# avrkitOnly.net
KiCad netlist of a schematic drawn in EAGLE
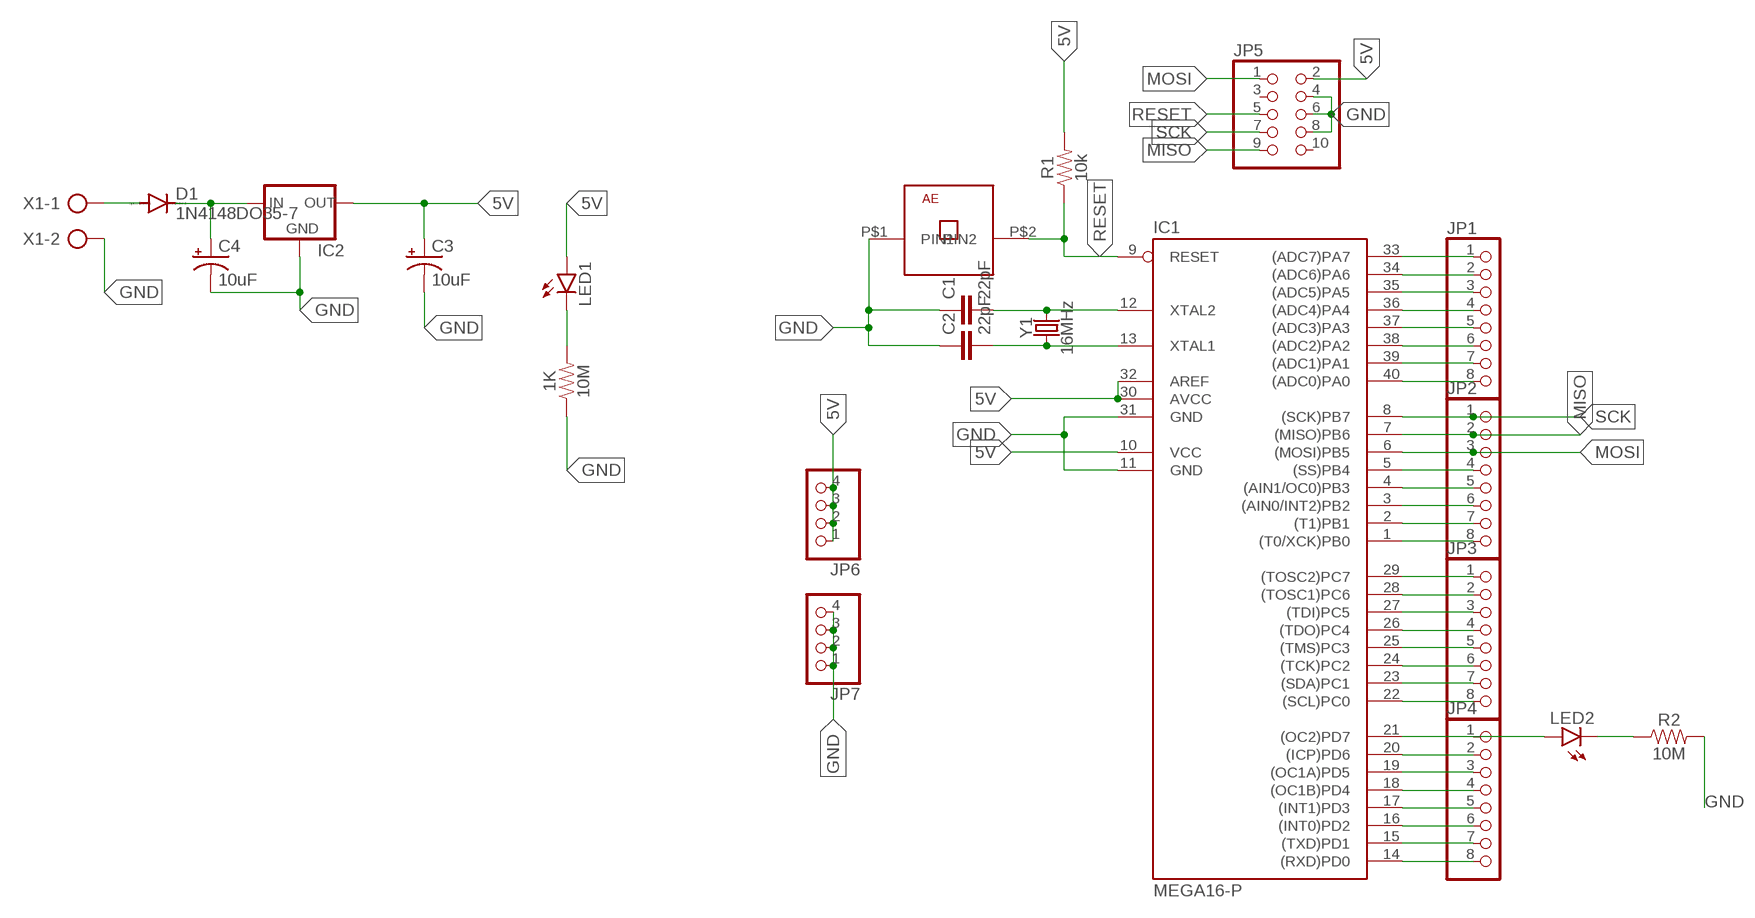
[diagram p0: schematic, sheet 1]

(export (version "E")
  (design (tool "Eeschema 10.0.6"))
  (components
    (comp (ref "1K")
      (value "10M")
      (footprint "eagle-import:AXIAL-0.3")
      (libsource (lib "eagle-import") (part "10MOHM-HORIZ-1/4W-5%"))
    )
    (comp (ref "C1")
      (value "22pF")
      (footprint "eagle-import:CAP-PTH-2.54")
      (libsource (lib "eagle-import") (part "22PF-PTH-2.54MM-200V-5%"))
    )
    (comp (ref "C2")
      (value "22pF")
      (footprint "eagle-import:CAP-PTH-2.54")
      (libsource (lib "eagle-import") (part "22PF-PTH-2.54MM-200V-5%"))
    )
    (comp (ref "C3")
      (value "10uF")
      (footprint "eagle-import:CPOL-RADIAL-2.5MM-5MM")
      (libsource (lib "eagle-import") (part "10UF-POLAR-RADIAL-2.5MM-25V-20%"))
    )
    (comp (ref "C4")
      (value "10uF")
      (footprint "eagle-import:CPOL-RADIAL-2.5MM-5MM")
      (libsource (lib "eagle-import") (part "10UF-POLAR-RADIAL-2.5MM-25V-20%"))
    )
    (comp (ref "D1")
      (value "1N4148DO35-7")
      (footprint "eagle-import:DO35-7")
      (libsource (lib "eagle-import") (part "1N4148DO35-7"))
    )
    (comp (ref "IC1")
      (value "MEGA16-P")
      (footprint "eagle-import:DIL40")
      (fields (field (name "MPN") "ATMEGA16-16PU"))
      (libsource (lib "eagle-import") (part "MEGA16-P"))
    )
    (comp (ref "IC2")
      (value "78XXS")
      (footprint "eagle-import:78XXS")
      (libsource (lib "eagle-import") (part "78XXS"))
    )
    (comp (ref "JP1")
      (value "PINHD-1X8")
      (footprint "eagle-import:1X08")
      (libsource (lib "eagle-import") (part "PINHD-1X8"))
    )
    (comp (ref "JP2")
      (value "PINHD-1X8")
      (footprint "eagle-import:1X08")
      (libsource (lib "eagle-import") (part "PINHD-1X8"))
    )
    (comp (ref "JP3")
      (value "PINHD-1X8")
      (footprint "eagle-import:1X08")
      (libsource (lib "eagle-import") (part "PINHD-1X8"))
    )
    (comp (ref "JP4")
      (value "PINHD-1X8")
      (footprint "eagle-import:1X08")
      (libsource (lib "eagle-import") (part "PINHD-1X8"))
    )
    (comp (ref "JP5")
      (value "PINHD-2X5")
      (footprint "eagle-import:2X05")
      (libsource (lib "eagle-import") (part "PINHD-2X5"))
    )
    (comp (ref "JP6")
      (value "PINHD-1X4")
      (footprint "eagle-import:1X04")
      (libsource (lib "eagle-import") (part "PINHD-1X4"))
    )
    (comp (ref "JP7")
      (value "PINHD-1X4")
      (footprint "eagle-import:1X04")
      (libsource (lib "eagle-import") (part "PINHD-1X4"))
    )
    (comp (ref "LED1")
      (value "LED3MM")
      (footprint "eagle-import:LED3MM")
      (libsource (lib "eagle-import") (part "LED3MM"))
    )
    (comp (ref "LED2")
      (value "LED3MM")
      (footprint "eagle-import:LED3MM")
      (libsource (lib "eagle-import") (part "LED3MM"))
    )
    (comp (ref "R1")
      (value "10k")
      (footprint "eagle-import:AXIAL-0.3")
      (libsource (lib "eagle-import") (part "10MOHM-HORIZ-1/4W-5%"))
    )
    (comp (ref "R2")
      (value "10M")
      (footprint "eagle-import:AXIAL-0.3")
      (libsource (lib "eagle-import") (part "10MOHM-HORIZ-1/4W-5%"))
    )
    (comp (ref "U$1")
      (value "PUSHBUTTON-AE")
      (footprint "eagle-import:PUSHBUTTON-AE")
      (libsource (lib "eagle-import") (part "PUSHBUTTON-AE"))
    )
    (comp (ref "X1")
      (value "AK500/2-H")
      (footprint "eagle-import:AK500_2-H")
      (libsource (lib "eagle-import") (part "AK500/2-H"))
    )
    (comp (ref "Y1")
      (value "16MHz")
      (footprint "eagle-import:HC49US")
      (libsource (lib "eagle-import") (part "CRYSTAL-16MHZPTH-HC49US"))
    )
  )
  (nets
    (net (code "1") (name "5V") (class "Default")
      (node (ref "C3") (pin "1") (pinfunction "+_1") (pintype "passive"))
      (node (ref "IC1") (pin "10") (pinfunction "VCC_10") (pintype "power_in"))
      (node (ref "IC1") (pin "30") (pinfunction "AVCC_30") (pintype "power_in"))
      (node (ref "IC1") (pin "32") (pinfunction "AREF_32") (pintype "passive"))
      (node (ref "IC2") (pin "OUT") (pinfunction "OUT_OUT") (pintype "passive"))
      (node (ref "JP5") (pin "2") (pinfunction "2_2") (pintype "passive"))
      (node (ref "JP6") (pin "1") (pinfunction "1_1") (pintype "passive"))
      (node (ref "JP6") (pin "2") (pinfunction "2_2") (pintype "passive"))
      (node (ref "JP6") (pin "3") (pinfunction "3_3") (pintype "passive"))
      (node (ref "JP6") (pin "4") (pinfunction "4_4") (pintype "passive"))
      (node (ref "LED1") (pin "A") (pinfunction "A_A") (pintype "passive"))
      (node (ref "R1") (pin "P$2") (pinfunction "2_P$2") (pintype "passive"))
    )
    (net (code "2") (name "GND") (class "Default")
      (node (ref "1K") (pin "P$1") (pinfunction "1_P$1") (pintype "passive"))
      (node (ref "C1") (pin "1") (pinfunction "1_1") (pintype "passive"))
      (node (ref "C2") (pin "1") (pinfunction "1_1") (pintype "passive"))
      (node (ref "C3") (pin "2") (pinfunction "-_2") (pintype "passive"))
      (node (ref "C4") (pin "2") (pinfunction "-_2") (pintype "passive"))
      (node (ref "IC1") (pin "11") (pinfunction "GND_11") (pintype "power_in"))
      (node (ref "IC1") (pin "31") (pinfunction "GND_31") (pintype "power_in"))
      (node (ref "IC2") (pin "GND") (pinfunction "GND_GND") (pintype "input"))
      (node (ref "JP5") (pin "4") (pinfunction "4_4") (pintype "passive"))
      (node (ref "JP5") (pin "6") (pinfunction "6_6") (pintype "passive"))
      (node (ref "JP5") (pin "8") (pinfunction "8_8") (pintype "passive"))
      (node (ref "JP7") (pin "1") (pinfunction "1_1") (pintype "passive"))
      (node (ref "JP7") (pin "2") (pinfunction "2_2") (pintype "passive"))
      (node (ref "JP7") (pin "3") (pinfunction "3_3") (pintype "passive"))
      (node (ref "JP7") (pin "4") (pinfunction "4_4") (pintype "passive"))
      (node (ref "R2") (pin "P$2") (pinfunction "2_P$2") (pintype "passive"))
      (node (ref "U$1") (pin "P$1") (pinfunction "PIN1_P$1") (pintype "bidirectional"))
      (node (ref "X1") (pin "2") (pinfunction "KL_2") (pintype "passive"))
    )
    (net (code "3") (name "MISO") (class "Default")
      (node (ref "IC1") (pin "7") (pinfunction "(MISO)PB6_7") (pintype "bidirectional"))
      (node (ref "JP2") (pin "2") (pinfunction "2_2") (pintype "passive"))
      (node (ref "JP5") (pin "9") (pinfunction "9_9") (pintype "passive"))
    )
    (net (code "4") (name "MOSI") (class "Default")
      (node (ref "IC1") (pin "6") (pinfunction "(MOSI)PB5_6") (pintype "bidirectional"))
      (node (ref "JP2") (pin "3") (pinfunction "3_3") (pintype "passive"))
      (node (ref "JP5") (pin "1") (pinfunction "1_1") (pintype "passive"))
    )
    (net (code "5") (name "Net-(1K-2)") (class "Default")
      (node (ref "1K") (pin "P$2") (pinfunction "2_P$2") (pintype "passive"))
      (node (ref "LED1") (pin "K") (pinfunction "C_K") (pintype "passive"))
    )
    (net (code "6") (name "Net-(C4-+)") (class "Default")
      (node (ref "C4") (pin "1") (pinfunction "+_1") (pintype "passive"))
      (node (ref "D1") (pin "C") (pinfunction "C_C") (pintype "passive"))
      (node (ref "IC2") (pin "IN") (pinfunction "IN_IN") (pintype "input"))
    )
    (net (code "7") (name "Net-(IC1-(ADC0)PA0)") (class "Default")
      (node (ref "IC1") (pin "40") (pinfunction "(ADC0)PA0_40") (pintype "bidirectional"))
      (node (ref "JP1") (pin "8") (pinfunction "8_8") (pintype "passive"))
    )
    (net (code "8") (name "Net-(IC1-(ADC1)PA1)") (class "Default")
      (node (ref "IC1") (pin "39") (pinfunction "(ADC1)PA1_39") (pintype "bidirectional"))
      (node (ref "JP1") (pin "7") (pinfunction "7_7") (pintype "passive"))
    )
    (net (code "9") (name "Net-(IC1-(ADC2)PA2)") (class "Default")
      (node (ref "IC1") (pin "38") (pinfunction "(ADC2)PA2_38") (pintype "bidirectional"))
      (node (ref "JP1") (pin "6") (pinfunction "6_6") (pintype "passive"))
    )
    (net (code "10") (name "Net-(IC1-(ADC3)PA3)") (class "Default")
      (node (ref "IC1") (pin "37") (pinfunction "(ADC3)PA3_37") (pintype "bidirectional"))
      (node (ref "JP1") (pin "5") (pinfunction "5_5") (pintype "passive"))
    )
    (net (code "11") (name "Net-(IC1-(ADC4)PA4)") (class "Default")
      (node (ref "IC1") (pin "36") (pinfunction "(ADC4)PA4_36") (pintype "bidirectional"))
      (node (ref "JP1") (pin "4") (pinfunction "4_4") (pintype "passive"))
    )
    (net (code "12") (name "Net-(IC1-(ADC5)PA5)") (class "Default")
      (node (ref "IC1") (pin "35") (pinfunction "(ADC5)PA5_35") (pintype "bidirectional"))
      (node (ref "JP1") (pin "3") (pinfunction "3_3") (pintype "passive"))
    )
    (net (code "13") (name "Net-(IC1-(ADC6)PA6)") (class "Default")
      (node (ref "IC1") (pin "34") (pinfunction "(ADC6)PA6_34") (pintype "bidirectional"))
      (node (ref "JP1") (pin "2") (pinfunction "2_2") (pintype "passive"))
    )
    (net (code "14") (name "Net-(IC1-(ADC7)PA7)") (class "Default")
      (node (ref "IC1") (pin "33") (pinfunction "(ADC7)PA7_33") (pintype "bidirectional"))
      (node (ref "JP1") (pin "1") (pinfunction "1_1") (pintype "passive"))
    )
    (net (code "15") (name "Net-(IC1-(AIN0{slash}INT2)PB2)") (class "Default")
      (node (ref "IC1") (pin "3") (pinfunction "(AIN0/INT2)PB2_3") (pintype "bidirectional"))
      (node (ref "JP2") (pin "6") (pinfunction "6_6") (pintype "passive"))
    )
    (net (code "16") (name "Net-(IC1-(AIN1{slash}OC0)PB3)") (class "Default")
      (node (ref "IC1") (pin "4") (pinfunction "(AIN1/OC0)PB3_4") (pintype "bidirectional"))
      (node (ref "JP2") (pin "5") (pinfunction "5_5") (pintype "passive"))
    )
    (net (code "17") (name "Net-(IC1-(ICP)PD6)") (class "Default")
      (node (ref "IC1") (pin "20") (pinfunction "(ICP)PD6_20") (pintype "bidirectional"))
      (node (ref "JP4") (pin "2") (pinfunction "2_2") (pintype "passive"))
    )
    (net (code "18") (name "Net-(IC1-(INT0)PD2)") (class "Default")
      (node (ref "IC1") (pin "16") (pinfunction "(INT0)PD2_16") (pintype "bidirectional"))
      (node (ref "JP4") (pin "6") (pinfunction "6_6") (pintype "passive"))
    )
    (net (code "19") (name "Net-(IC1-(INT1)PD3)") (class "Default")
      (node (ref "IC1") (pin "17") (pinfunction "(INT1)PD3_17") (pintype "bidirectional"))
      (node (ref "JP4") (pin "5") (pinfunction "5_5") (pintype "passive"))
    )
    (net (code "20") (name "Net-(IC1-(OC1A)PD5)") (class "Default")
      (node (ref "IC1") (pin "19") (pinfunction "(OC1A)PD5_19") (pintype "bidirectional"))
      (node (ref "JP4") (pin "3") (pinfunction "3_3") (pintype "passive"))
    )
    (net (code "21") (name "Net-(IC1-(OC1B)PD4)") (class "Default")
      (node (ref "IC1") (pin "18") (pinfunction "(OC1B)PD4_18") (pintype "bidirectional"))
      (node (ref "JP4") (pin "4") (pinfunction "4_4") (pintype "passive"))
    )
    (net (code "22") (name "Net-(IC1-(OC2)PD7)") (class "Default")
      (node (ref "IC1") (pin "21") (pinfunction "(OC2)PD7_21") (pintype "bidirectional"))
      (node (ref "JP4") (pin "1") (pinfunction "1_1") (pintype "passive"))
      (node (ref "LED2") (pin "A") (pinfunction "A_A") (pintype "passive"))
    )
    (net (code "23") (name "Net-(IC1-(RXD)PD0)") (class "Default")
      (node (ref "IC1") (pin "14") (pinfunction "(RXD)PD0_14") (pintype "bidirectional"))
      (node (ref "JP4") (pin "8") (pinfunction "8_8") (pintype "passive"))
    )
    (net (code "24") (name "Net-(IC1-(SCL)PC0)") (class "Default")
      (node (ref "IC1") (pin "22") (pinfunction "(SCL)PC0_22") (pintype "bidirectional"))
      (node (ref "JP3") (pin "8") (pinfunction "8_8") (pintype "passive"))
    )
    (net (code "25") (name "Net-(IC1-(SDA)PC1)") (class "Default")
      (node (ref "IC1") (pin "23") (pinfunction "(SDA)PC1_23") (pintype "bidirectional"))
      (node (ref "JP3") (pin "7") (pinfunction "7_7") (pintype "passive"))
    )
    (net (code "26") (name "Net-(IC1-(SS)PB4)") (class "Default")
      (node (ref "IC1") (pin "5") (pinfunction "(SS)PB4_5") (pintype "bidirectional"))
      (node (ref "JP2") (pin "4") (pinfunction "4_4") (pintype "passive"))
    )
    (net (code "27") (name "Net-(IC1-(T0{slash}XCK)PB0)") (class "Default")
      (node (ref "IC1") (pin "1") (pinfunction "(T0/XCK)PB0_1") (pintype "bidirectional"))
      (node (ref "JP2") (pin "8") (pinfunction "8_8") (pintype "passive"))
    )
    (net (code "28") (name "Net-(IC1-(T1)PB1)") (class "Default")
      (node (ref "IC1") (pin "2") (pinfunction "(T1)PB1_2") (pintype "bidirectional"))
      (node (ref "JP2") (pin "7") (pinfunction "7_7") (pintype "passive"))
    )
    (net (code "29") (name "Net-(IC1-(TCK)PC2)") (class "Default")
      (node (ref "IC1") (pin "24") (pinfunction "(TCK)PC2_24") (pintype "bidirectional"))
      (node (ref "JP3") (pin "6") (pinfunction "6_6") (pintype "passive"))
    )
    (net (code "30") (name "Net-(IC1-(TDI)PC5)") (class "Default")
      (node (ref "IC1") (pin "27") (pinfunction "(TDI)PC5_27") (pintype "bidirectional"))
      (node (ref "JP3") (pin "3") (pinfunction "3_3") (pintype "passive"))
    )
    (net (code "31") (name "Net-(IC1-(TDO)PC4)") (class "Default")
      (node (ref "IC1") (pin "26") (pinfunction "(TDO)PC4_26") (pintype "bidirectional"))
      (node (ref "JP3") (pin "4") (pinfunction "4_4") (pintype "passive"))
    )
    (net (code "32") (name "Net-(IC1-(TMS)PC3)") (class "Default")
      (node (ref "IC1") (pin "25") (pinfunction "(TMS)PC3_25") (pintype "bidirectional"))
      (node (ref "JP3") (pin "5") (pinfunction "5_5") (pintype "passive"))
    )
    (net (code "33") (name "Net-(IC1-(TOSC1)PC6)") (class "Default")
      (node (ref "IC1") (pin "28") (pinfunction "(TOSC1)PC6_28") (pintype "bidirectional"))
      (node (ref "JP3") (pin "2") (pinfunction "2_2") (pintype "passive"))
    )
    (net (code "34") (name "Net-(IC1-(TOSC2)PC7)") (class "Default")
      (node (ref "IC1") (pin "29") (pinfunction "(TOSC2)PC7_29") (pintype "bidirectional"))
      (node (ref "JP3") (pin "1") (pinfunction "1_1") (pintype "passive"))
    )
    (net (code "35") (name "Net-(IC1-(TXD)PD1)") (class "Default")
      (node (ref "IC1") (pin "15") (pinfunction "(TXD)PD1_15") (pintype "bidirectional"))
      (node (ref "JP4") (pin "7") (pinfunction "7_7") (pintype "passive"))
    )
    (net (code "36") (name "Net-(IC1-XTAL1)") (class "Default")
      (node (ref "C2") (pin "2") (pinfunction "2_2") (pintype "passive"))
      (node (ref "IC1") (pin "13") (pinfunction "XTAL1_13") (pintype "bidirectional"))
      (node (ref "Y1") (pin "1") (pinfunction "1_1") (pintype "passive"))
    )
    (net (code "37") (name "Net-(IC1-XTAL2)") (class "Default")
      (node (ref "C1") (pin "2") (pinfunction "2_2") (pintype "passive"))
      (node (ref "IC1") (pin "12") (pinfunction "XTAL2_12") (pintype "bidirectional"))
      (node (ref "Y1") (pin "2") (pinfunction "2_2") (pintype "passive"))
    )
    (net (code "38") (name "Net-(LED2-C)") (class "Default")
      (node (ref "LED2") (pin "K") (pinfunction "C_K") (pintype "passive"))
      (node (ref "R2") (pin "P$1") (pinfunction "1_P$1") (pintype "passive"))
    )
    (net (code "39") (name "Net-(X1A-KL)") (class "Default")
      (node (ref "D1") (pin "A") (pinfunction "A_A") (pintype "passive"))
      (node (ref "X1") (pin "1") (pinfunction "KL_1") (pintype "passive"))
    )
    (net (code "40") (name "RESET") (class "Default")
      (node (ref "IC1") (pin "9") (pinfunction "RESET_9") (pintype "input"))
      (node (ref "JP5") (pin "5") (pinfunction "5_5") (pintype "passive"))
      (node (ref "R1") (pin "P$1") (pinfunction "1_P$1") (pintype "passive"))
      (node (ref "U$1") (pin "P$2") (pinfunction "PIN2_P$2") (pintype "bidirectional"))
    )
    (net (code "41") (name "SCK") (class "Default")
      (node (ref "IC1") (pin "8") (pinfunction "(SCK)PB7_8") (pintype "bidirectional"))
      (node (ref "JP2") (pin "1") (pinfunction "1_1") (pintype "passive"))
      (node (ref "JP5") (pin "7") (pinfunction "7_7") (pintype "passive"))
    )
    (net (code "42") (name "unconnected-(JP5-Pad3)") (class "Default")
      (node (ref "JP5") (pin "3") (pinfunction "3_3") (pintype "passive"))
    )
    (net (code "43") (name "unconnected-(JP5-Pad10)") (class "Default")
      (node (ref "JP5") (pin "10") (pinfunction "10_10") (pintype "passive"))
    )
  )
)
